# Connector_Battery.net
KiCad netlist of a schematic drawn in Altium Designer
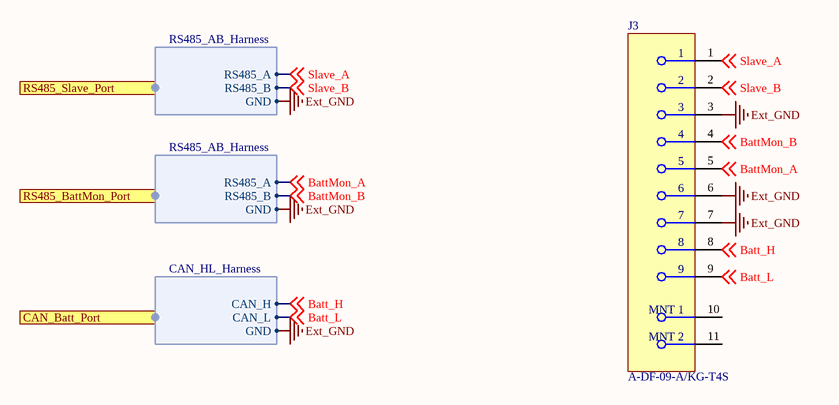
[diagram p0: Connector_Battery.SchDoc]

(export (version "E")
  (design (tool "Eeschema 10.0.6"))
  (components
    (comp (ref "J3")
      (value "A-DF-09-A/KG-T4S")
      (footprint "FP-A-DF_09_A-KG-T4S-MFG")
      (description "Conn D-Sub F 9 POS 1.38mm Solder RA Thru-Hole 9 Terminal 1 Port")
      (fields (field (name "DIGI-KEY_PART_NUMBER") "AE10924-ND"))
      (libsource (lib "Altium Content Vault") (part "A-DF_09_A-KG-T4S"))
    )
  )
  (nets
    (net (code "5") (name "BattMon_A") (class "Default")
      (node (ref "J3") (pin "5") (pinfunction "5_5") (pintype "passive"))
    )
    (net (code "6") (name "BattMon_B") (class "Default")
      (node (ref "J3") (pin "4") (pinfunction "4_4") (pintype "passive"))
    )
    (net (code "7") (name "Batt_H") (class "Default")
      (node (ref "J3") (pin "8") (pinfunction "8_8") (pintype "passive"))
    )
    (net (code "8") (name "Batt_L") (class "Default")
      (node (ref "J3") (pin "9") (pinfunction "9_9") (pintype "passive"))
    )
    (net (code "9") (name "Ext_GND") (class "Default")
      (node (ref "J3") (pin "3") (pinfunction "3_3") (pintype "passive"))
      (node (ref "J3") (pin "6") (pinfunction "6_6") (pintype "passive"))
      (node (ref "J3") (pin "7") (pinfunction "7_7") (pintype "passive"))
    )
    (net (code "10") (name "Slave_A") (class "Default")
      (node (ref "J3") (pin "1") (pinfunction "1_1") (pintype "passive"))
    )
    (net (code "11") (name "Slave_B") (class "Default")
      (node (ref "J3") (pin "2") (pinfunction "2_2") (pintype "passive"))
    )
    (net (code "12") (name "unconnected-(J3-MNT_1-Pad10)") (class "Default")
      (node (ref "J3") (pin "10") (pinfunction "MNT_1_10") (pintype "passive"))
    )
    (net (code "13") (name "unconnected-(J3-MNT_2-Pad11)") (class "Default")
      (node (ref "J3") (pin "11") (pinfunction "MNT_2_11") (pintype "passive"))
    )
  )
)
